# 0_2a.net
KiCad netlist of a schematic drawn in EAGLE
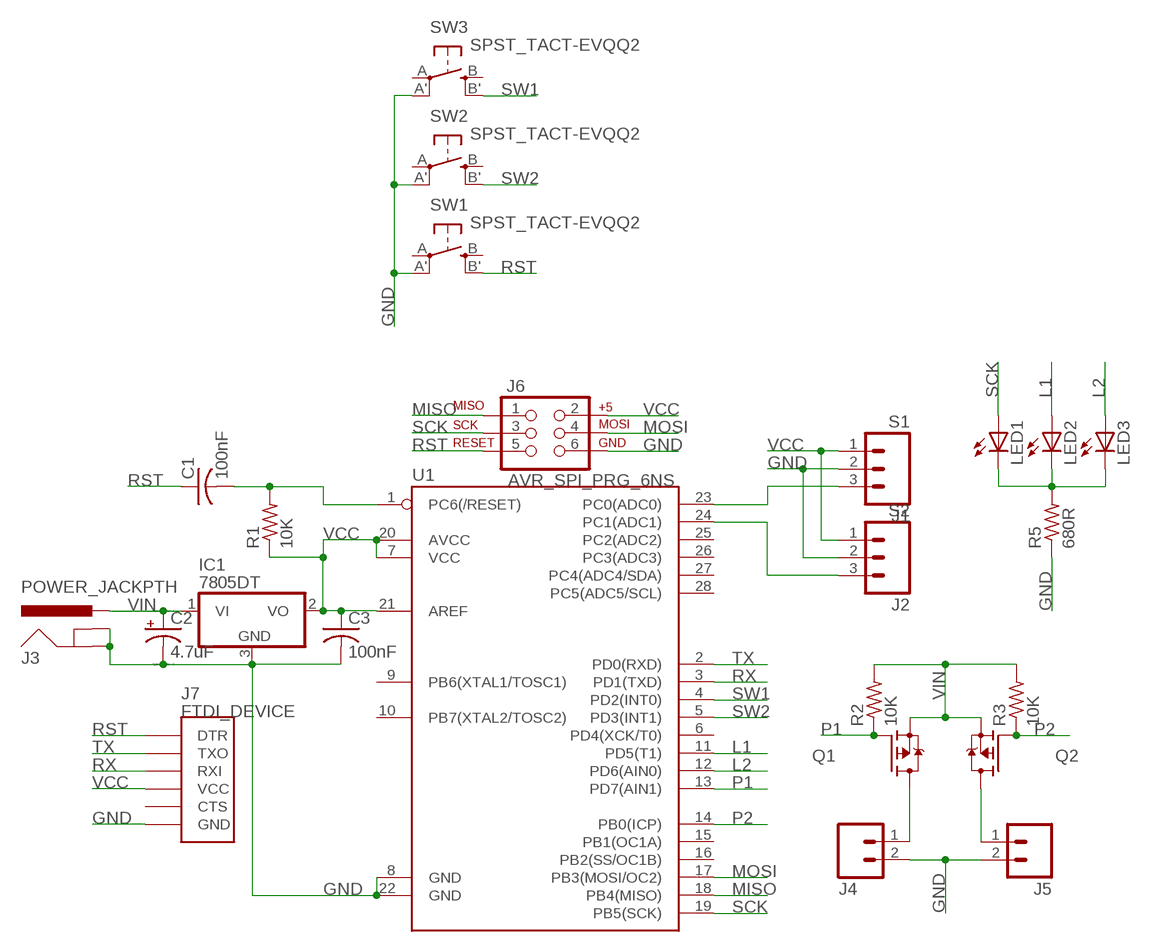
[diagram p0: schematic, sheet 1]

(export (version "E")
  (design (tool "Eeschema 10.0.6"))
  (components
    (comp (ref "C1")
      (value "100nF")
      (footprint "eagle-import:C1206K")
      (libsource (lib "eagle-import") (part "C-USC1206K"))
    )
    (comp (ref "C2")
      (value "4.7uF")
      (footprint "eagle-import:153CLV-0405")
      (libsource (lib "eagle-import") (part "CPOL-US153CLV-0405"))
    )
    (comp (ref "C3")
      (value "100nF")
      (footprint "eagle-import:C1206K")
      (libsource (lib "eagle-import") (part "resistor_C-USC1206K"))
    )
    (comp (ref "IC1")
      (value "7805DT")
      (footprint "eagle-import:TO252")
      (libsource (lib "eagle-import") (part "78DT05"))
    )
    (comp (ref "J1")
      (value "S1")
      (footprint "eagle-import:MOLEX-1X3")
      (libsource (lib "eagle-import") (part "M03POLAR"))
    )
    (comp (ref "J2")
      (value "S2")
      (footprint "eagle-import:MOLEX-1X3")
      (libsource (lib "eagle-import") (part "M03POLAR"))
    )
    (comp (ref "J3")
      (value "POWER_JACKPTH")
      (footprint "eagle-import:POWER_JACK_PTH")
      (libsource (lib "eagle-import") (part "POWER_JACKPTH"))
    )
    (comp (ref "J4")
      (value "M02POLAR")
      (footprint "eagle-import:MOLEX-1X2")
      (libsource (lib "eagle-import") (part "M02POLAR"))
    )
    (comp (ref "J5")
      (value "M02POLAR")
      (footprint "eagle-import:MOLEX-1X2")
      (libsource (lib "eagle-import") (part "M02POLAR"))
    )
    (comp (ref "J6")
      (value "AVR_SPI_PRG_6NS")
      (footprint "eagle-import:2X3-NS")
      (libsource (lib "eagle-import") (part "AVR_SPI_PRG_6NS"))
    )
    (comp (ref "J7")
      (value "FTDI_DEVICE")
      (footprint "eagle-import:FTDI_DEVICE_SIDE")
      (libsource (lib "eagle-import") (part "FTDI_DEVICE"))
    )
    (comp (ref "LED1")
      (value "LED3MM")
      (footprint "eagle-import:LED3MM")
      (libsource (lib "eagle-import") (part "LED3MM"))
    )
    (comp (ref "LED2")
      (value "LED3MM")
      (footprint "eagle-import:LED3MM")
      (libsource (lib "eagle-import") (part "LED3MM"))
    )
    (comp (ref "LED3")
      (value "LED3MM")
      (footprint "eagle-import:LED3MM")
      (libsource (lib "eagle-import") (part "LED3MM"))
    )
    (comp (ref "Q1")
      (value "FDD4141TO252")
      (footprint "eagle-import:TO252")
      (libsource (lib "eagle-import") (part "FDD4141TO252"))
    )
    (comp (ref "Q2")
      (value "FDD4141TO252")
      (footprint "eagle-import:TO252")
      (libsource (lib "eagle-import") (part "FDD4141TO252"))
    )
    (comp (ref "R1")
      (value "10K")
      (footprint "eagle-import:R0805")
      (libsource (lib "eagle-import") (part "R-US_R0805"))
    )
    (comp (ref "R2")
      (value "10K")
      (footprint "eagle-import:R0805")
      (libsource (lib "eagle-import") (part "R-US_R0805"))
    )
    (comp (ref "R3")
      (value "10K")
      (footprint "eagle-import:R0805")
      (libsource (lib "eagle-import") (part "R-US_R0805"))
    )
    (comp (ref "R5")
      (value "680R")
      (footprint "eagle-import:R0805")
      (libsource (lib "eagle-import") (part "resistor_R-US_R0805"))
    )
    (comp (ref "SW1")
      (value "SPST_TACT-EVQQ2")
      (footprint "eagle-import:EVQ-Q2")
      (libsource (lib "eagle-import") (part "SPST_TACT-EVQQ2"))
    )
    (comp (ref "SW2")
      (value "SPST_TACT-EVQQ2")
      (footprint "eagle-import:EVQ-Q2")
      (libsource (lib "eagle-import") (part "SPST_TACT-EVQQ2"))
    )
    (comp (ref "SW3")
      (value "SPST_TACT-EVQQ2")
      (footprint "eagle-import:EVQ-Q2")
      (libsource (lib "eagle-import") (part "SPST_TACT-EVQQ2"))
    )
    (comp (ref "U1")
      (value "ATMEGA328P_PDIP")
      (footprint "eagle-import:DIL28-3")
      (libsource (lib "eagle-import") (part "ATMEGA328P_PDIP"))
    )
  )
  (nets
    (net (code "1") (name "/GND") (class "Default")
      (node (ref "C2") (pin "-") (pinfunction "-_-") (pintype "passive"))
      (node (ref "C3") (pin "2") (pinfunction "2_2") (pintype "passive"))
      (node (ref "IC1") (pin "3") (pinfunction "GND_3") (pintype "passive"))
      (node (ref "J1") (pin "2") (pinfunction "2_2") (pintype "passive"))
      (node (ref "J2") (pin "2") (pinfunction "2_2") (pintype "passive"))
      (node (ref "J3") (pin "GND") (pinfunction "GND_GND") (pintype "bidirectional"))
      (node (ref "J3") (pin "GNDBREAK") (pinfunction "GNDBREAK_GNDBREAK") (pintype "bidirectional"))
      (node (ref "J4") (pin "2") (pinfunction "2_2") (pintype "passive"))
      (node (ref "J5") (pin "2") (pinfunction "2_2") (pintype "passive"))
      (node (ref "J6") (pin "6") (pinfunction "6_6") (pintype "passive"))
      (node (ref "J7") (pin "P$6") (pinfunction "GND_P$6") (pintype "bidirectional"))
      (node (ref "R5") (pin "1") (pinfunction "1_1") (pintype "passive"))
      (node (ref "SW1") (pin "A'") (pinfunction "P1_A'") (pintype "passive"))
      (node (ref "SW2") (pin "A'") (pinfunction "P1_A'") (pintype "passive"))
      (node (ref "SW3") (pin "A'") (pinfunction "P1_A'") (pintype "passive"))
      (node (ref "U1") (pin "22") (pinfunction "GND_22") (pintype "bidirectional"))
      (node (ref "U1") (pin "8") (pinfunction "GND_8") (pintype "bidirectional"))
    )
    (net (code "2") (name "/L1") (class "Default")
      (node (ref "LED2") (pin "A") (pinfunction "A_A") (pintype "passive"))
      (node (ref "U1") (pin "11") (pinfunction "PD5(T1)_11") (pintype "bidirectional"))
    )
    (net (code "3") (name "/L2") (class "Default")
      (node (ref "LED3") (pin "A") (pinfunction "A_A") (pintype "passive"))
      (node (ref "U1") (pin "12") (pinfunction "PD6(AIN0)_12") (pintype "bidirectional"))
    )
    (net (code "4") (name "/MISO") (class "Default")
      (node (ref "J6") (pin "1") (pinfunction "1_1") (pintype "passive"))
      (node (ref "U1") (pin "18") (pinfunction "PB4(MISO)_18") (pintype "bidirectional"))
    )
    (net (code "5") (name "/MOSI") (class "Default")
      (node (ref "J6") (pin "4") (pinfunction "4_4") (pintype "passive"))
      (node (ref "U1") (pin "17") (pinfunction "PB3(MOSI/OC2)_17") (pintype "bidirectional"))
    )
    (net (code "6") (name "/P1") (class "Default")
      (node (ref "Q1") (pin "1") (pinfunction "G_1") (pintype "passive"))
      (node (ref "R2") (pin "1") (pinfunction "1_1") (pintype "passive"))
      (node (ref "U1") (pin "13") (pinfunction "PD7(AIN1)_13") (pintype "bidirectional"))
    )
    (net (code "7") (name "/P2") (class "Default")
      (node (ref "Q2") (pin "1") (pinfunction "G_1") (pintype "passive"))
      (node (ref "R3") (pin "1") (pinfunction "1_1") (pintype "passive"))
      (node (ref "U1") (pin "14") (pinfunction "PB0(ICP)_14") (pintype "bidirectional"))
    )
    (net (code "8") (name "/RST") (class "Default")
      (node (ref "C1") (pin "1") (pinfunction "1_1") (pintype "passive"))
      (node (ref "J6") (pin "5") (pinfunction "5_5") (pintype "passive"))
      (node (ref "J7") (pin "P$1") (pinfunction "DTR_P$1") (pintype "bidirectional"))
      (node (ref "SW1") (pin "B'") (pinfunction "S1_B'") (pintype "passive"))
    )
    (net (code "9") (name "/RX") (class "Default")
      (node (ref "J7") (pin "P$3") (pinfunction "RXI_P$3") (pintype "bidirectional"))
      (node (ref "U1") (pin "3") (pinfunction "PD1(TXD)_3") (pintype "bidirectional"))
    )
    (net (code "10") (name "/SCK") (class "Default")
      (node (ref "J6") (pin "3") (pinfunction "3_3") (pintype "passive"))
      (node (ref "LED1") (pin "A") (pinfunction "A_A") (pintype "passive"))
      (node (ref "U1") (pin "19") (pinfunction "PB5(SCK)_19") (pintype "bidirectional"))
    )
    (net (code "11") (name "/SW1") (class "Default")
      (node (ref "SW3") (pin "B'") (pinfunction "S1_B'") (pintype "passive"))
      (node (ref "U1") (pin "4") (pinfunction "PD2(INT0)_4") (pintype "bidirectional"))
    )
    (net (code "12") (name "/SW2") (class "Default")
      (node (ref "SW2") (pin "B'") (pinfunction "S1_B'") (pintype "passive"))
      (node (ref "U1") (pin "5") (pinfunction "PD3(INT1)_5") (pintype "bidirectional"))
    )
    (net (code "13") (name "/TX") (class "Default")
      (node (ref "J7") (pin "P$2") (pinfunction "TXO_P$2") (pintype "bidirectional"))
      (node (ref "U1") (pin "2") (pinfunction "PD0(RXD)_2") (pintype "bidirectional"))
    )
    (net (code "14") (name "/VCC") (class "Default")
      (node (ref "C3") (pin "1") (pinfunction "1_1") (pintype "passive"))
      (node (ref "IC1") (pin "2") (pinfunction "VO_2") (pintype "passive"))
      (node (ref "J1") (pin "1") (pinfunction "1_1") (pintype "passive"))
      (node (ref "J2") (pin "1") (pinfunction "1_1") (pintype "passive"))
      (node (ref "J6") (pin "2") (pinfunction "2_2") (pintype "passive"))
      (node (ref "J7") (pin "P$4") (pinfunction "VCC_P$4") (pintype "bidirectional"))
      (node (ref "R1") (pin "1") (pinfunction "1_1") (pintype "passive"))
      (node (ref "U1") (pin "20") (pinfunction "AVCC_20") (pintype "bidirectional"))
      (node (ref "U1") (pin "21") (pinfunction "AREF_21") (pintype "bidirectional"))
      (node (ref "U1") (pin "7") (pinfunction "VCC_7") (pintype "bidirectional"))
    )
    (net (code "15") (name "/VIN") (class "Default")
      (node (ref "C2") (pin "+") (pinfunction "+_+") (pintype "passive"))
      (node (ref "IC1") (pin "1") (pinfunction "VI_1") (pintype "input"))
      (node (ref "J3") (pin "PWR") (pinfunction "PWR_PWR") (pintype "bidirectional"))
      (node (ref "Q1") (pin "2") (pinfunction "S_2") (pintype "passive"))
      (node (ref "Q2") (pin "2") (pinfunction "S_2") (pintype "passive"))
      (node (ref "R2") (pin "2") (pinfunction "2_2") (pintype "passive"))
      (node (ref "R3") (pin "2") (pinfunction "2_2") (pintype "passive"))
    )
    (net (code "16") (name "Net-(LED1-C)") (class "Default")
      (node (ref "LED1") (pin "K") (pinfunction "C_K") (pintype "passive"))
      (node (ref "LED2") (pin "K") (pinfunction "C_K") (pintype "passive"))
      (node (ref "LED3") (pin "K") (pinfunction "C_K") (pintype "passive"))
      (node (ref "R5") (pin "2") (pinfunction "2_2") (pintype "passive"))
    )
    (net (code "17") (name "Net-(Q1-D)") (class "Default")
      (node (ref "J4") (pin "1") (pinfunction "1_1") (pintype "passive"))
      (node (ref "Q1") (pin "3") (pinfunction "D_3") (pintype "passive"))
    )
    (net (code "18") (name "Net-(Q2-D)") (class "Default")
      (node (ref "J5") (pin "1") (pinfunction "1_1") (pintype "passive"))
      (node (ref "Q2") (pin "3") (pinfunction "D_3") (pintype "passive"))
    )
    (net (code "19") (name "Net-(U1-PC0(ADC0))") (class "Default")
      (node (ref "J1") (pin "3") (pinfunction "3_3") (pintype "passive"))
      (node (ref "U1") (pin "23") (pinfunction "PC0(ADC0)_23") (pintype "bidirectional"))
    )
    (net (code "20") (name "Net-(U1-PC1(ADC1))") (class "Default")
      (node (ref "J2") (pin "3") (pinfunction "3_3") (pintype "passive"))
      (node (ref "U1") (pin "24") (pinfunction "PC1(ADC1)_24") (pintype "bidirectional"))
    )
    (net (code "21") (name "Net-(U1-PC6({slash}RESET))") (class "Default")
      (node (ref "C1") (pin "2") (pinfunction "2_2") (pintype "passive"))
      (node (ref "R1") (pin "2") (pinfunction "2_2") (pintype "passive"))
      (node (ref "U1") (pin "1") (pinfunction "PC6(/RESET)_1") (pintype "bidirectional"))
    )
    (net (code "22") (name "unconnected-(J7-CTS-PadP$5)") (class "Default")
      (node (ref "J7") (pin "P$5") (pinfunction "CTS_P$5") (pintype "bidirectional"))
    )
    (net (code "23") (name "unconnected-(SW1-P-PadA)") (class "Default")
      (node (ref "SW1") (pin "A") (pinfunction "P_A") (pintype "passive"))
    )
    (net (code "24") (name "unconnected-(SW1-S-PadB)") (class "Default")
      (node (ref "SW1") (pin "B") (pinfunction "S_B") (pintype "passive"))
    )
    (net (code "25") (name "unconnected-(SW2-P-PadA)") (class "Default")
      (node (ref "SW2") (pin "A") (pinfunction "P_A") (pintype "passive"))
    )
    (net (code "26") (name "unconnected-(SW2-S-PadB)") (class "Default")
      (node (ref "SW2") (pin "B") (pinfunction "S_B") (pintype "passive"))
    )
    (net (code "27") (name "unconnected-(SW3-P-PadA)") (class "Default")
      (node (ref "SW3") (pin "A") (pinfunction "P_A") (pintype "passive"))
    )
    (net (code "28") (name "unconnected-(SW3-S-PadB)") (class "Default")
      (node (ref "SW3") (pin "B") (pinfunction "S_B") (pintype "passive"))
    )
    (net (code "29") (name "unconnected-(U1-PB1(OC1A)-Pad15)") (class "Default")
      (node (ref "U1") (pin "15") (pinfunction "PB1(OC1A)_15") (pintype "bidirectional"))
    )
    (net (code "30") (name "unconnected-(U1-PB2(SS{slash}OC1B)-Pad16)") (class "Default")
      (node (ref "U1") (pin "16") (pinfunction "PB2(SS/OC1B)_16") (pintype "bidirectional"))
    )
    (net (code "31") (name "unconnected-(U1-PB6(XTAL1{slash}TOSC1)-Pad9)") (class "Default")
      (node (ref "U1") (pin "9") (pinfunction "PB6(XTAL1/TOSC1)_9") (pintype "bidirectional"))
    )
    (net (code "32") (name "unconnected-(U1-PB7(XTAL2{slash}TOSC2)-Pad10)") (class "Default")
      (node (ref "U1") (pin "10") (pinfunction "PB7(XTAL2/TOSC2)_10") (pintype "bidirectional"))
    )
    (net (code "33") (name "unconnected-(U1-PC2(ADC2)-Pad25)") (class "Default")
      (node (ref "U1") (pin "25") (pinfunction "PC2(ADC2)_25") (pintype "bidirectional"))
    )
    (net (code "34") (name "unconnected-(U1-PC3(ADC3)-Pad26)") (class "Default")
      (node (ref "U1") (pin "26") (pinfunction "PC3(ADC3)_26") (pintype "bidirectional"))
    )
    (net (code "35") (name "unconnected-(U1-PC4(ADC4{slash}SDA)-Pad27)") (class "Default")
      (node (ref "U1") (pin "27") (pinfunction "PC4(ADC4/SDA)_27") (pintype "bidirectional"))
    )
    (net (code "36") (name "unconnected-(U1-PC5(ADC5{slash}SCL)-Pad28)") (class "Default")
      (node (ref "U1") (pin "28") (pinfunction "PC5(ADC5/SCL)_28") (pintype "bidirectional"))
    )
    (net (code "37") (name "unconnected-(U1-PD4(XCK{slash}T0)-Pad6)") (class "Default")
      (node (ref "U1") (pin "6") (pinfunction "PD4(XCK/T0)_6") (pintype "bidirectional"))
    )
  )
)
